# WirelessPower.net
KiCad netlist of a schematic drawn in Altium Designer
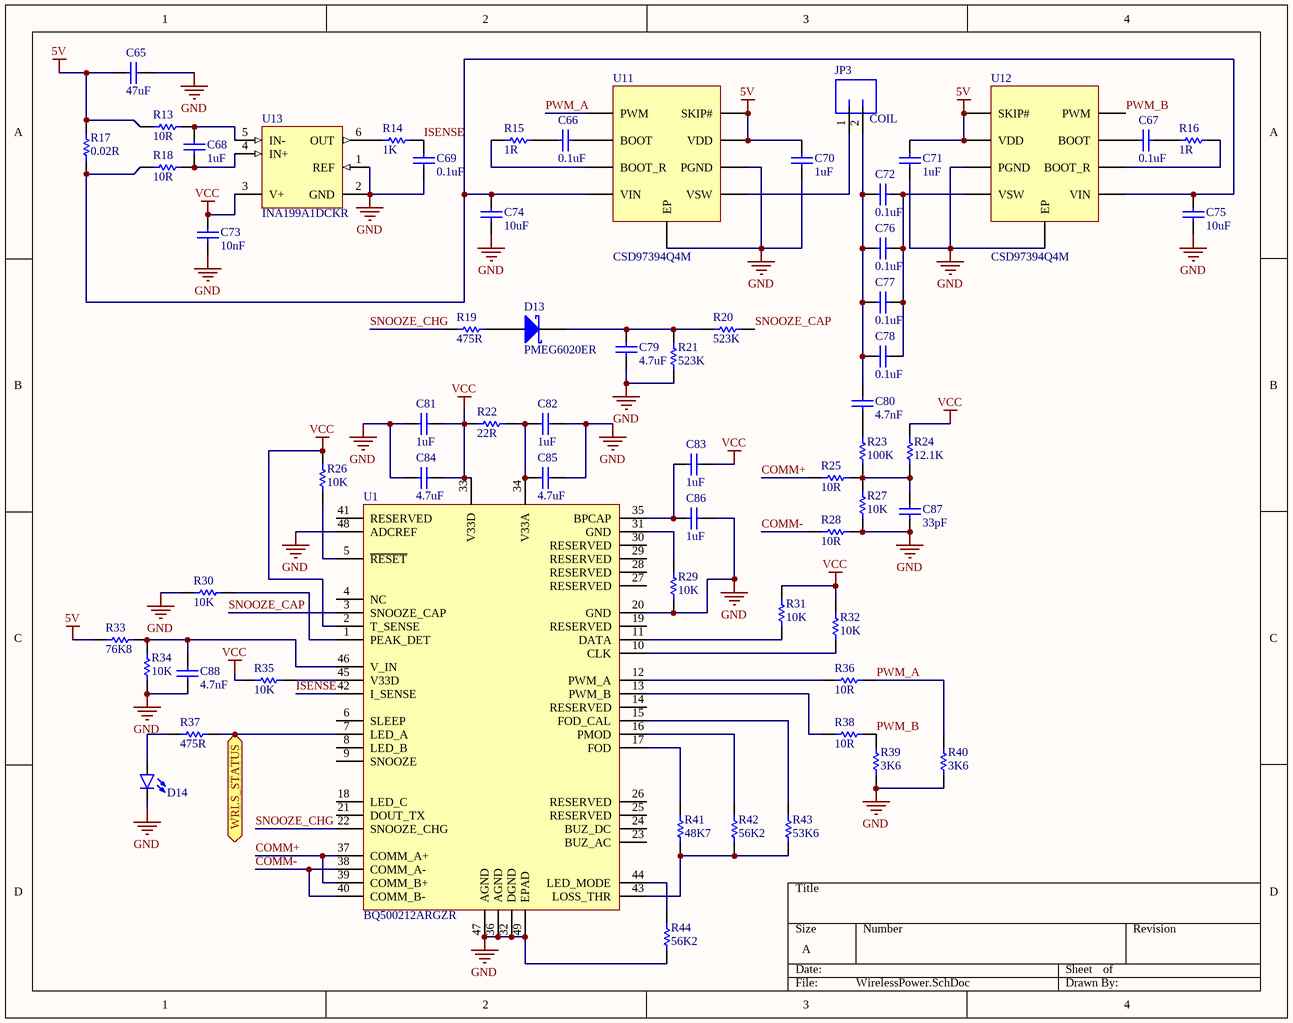
[diagram p0: WirelessPower.SchDoc]

(export (version "E")
  (design (tool "Eeschema 10.0.6"))
  (components
    (comp (ref "C65")
      (value "47uF")
      (footprint "C1210[3225X250]")
      (description "47uF 6.3V 10% 1210 (3225 Metric)")
      (fields (field (name "PARTNUMBER") "GRM32ER70J476KE20L") (field (name "MANUFACTURER") "Murata"))
      (libsource (lib "Capacitors") (part "CAP_47uF_6.3V_1210_10%"))
    )
    (comp (ref "C66")
      (value "0.1uF")
      (footprint "C0402[1005X55]")
      (description "0.1uF 100V 10% 0402 (1005 Metric)")
      (fields (field (name "PARTNUMBER") "GRM155R62A104KE14D") (field (name "MANUFACTURER") "Murata"))
      (libsource (lib "Capacitors") (part "CAP_0.1uF_100V_0402_10%"))
    )
    (comp (ref "C67")
      (value "0.1uF")
      (footprint "C0402[1005X55]")
      (description "0.1uF 100V 10% 0402 (1005 Metric)")
      (fields (field (name "PARTNUMBER") "GRM155R62A104KE14D") (field (name "MANUFACTURER") "Murata"))
      (libsource (lib "Capacitors") (part "CAP_0.1uF_100V_0402_10%"))
    )
    (comp (ref "C68")
      (value "1uF")
      (footprint "C0402[1005X55]")
      (description "1uF 6.3V 10% 0402 (1005 Metric)")
      (fields (field (name "PARTNUMBER") "GRM155R70J105KA12D") (field (name "MANUFACTURER") "Murata"))
      (libsource (lib "Capacitors") (part "CAP_1uF_6.3V_0402_10%"))
    )
    (comp (ref "C69")
      (value "0.1uF")
      (footprint "C0402[1005X55]")
      (description "0.1uF 6.3V 10% 0402 (1005 Metric)")
      (fields (field (name "PARTNUMBER") "GRM155R70J104KA01D") (field (name "MANUFACTURER") "Murata"))
      (libsource (lib "Capacitors") (part "CAP_0.1uF_6.3V_0402_10%"))
    )
    (comp (ref "C70")
      (value "1uF")
      (footprint "C0402[1005X55]")
      (description "1uF 6.3V 10% 0402 (1005 Metric)")
      (fields (field (name "PARTNUMBER") "GRM155R70J105KA12D") (field (name "MANUFACTURER") "Murata"))
      (libsource (lib "Capacitors") (part "CAP_1uF_6.3V_0402_10%"))
    )
    (comp (ref "C71")
      (value "1uF")
      (footprint "C0402[1005X55]")
      (description "1uF 6.3V 10% 0402 (1005 Metric)")
      (fields (field (name "PARTNUMBER") "GRM155R70J105KA12D") (field (name "MANUFACTURER") "Murata"))
      (libsource (lib "Capacitors") (part "CAP_1uF_6.3V_0402_10%"))
    )
    (comp (ref "C72")
      (value "0.1uF")
      (footprint "C0402[1005X55]")
      (description "0.1uF 100V 10% 0402 (1005 Metric)")
      (fields (field (name "PARTNUMBER") "GRM155R62A104KE14D") (field (name "MANUFACTURER") "Murata"))
      (libsource (lib "Capacitors") (part "CAP_0.1uF_100V_0402_10%"))
    )
    (comp (ref "C73")
      (value "10nF")
      (footprint "C0402[1005X55]")
      (description "10nF 50V 10% 0402 (1005 Metric)")
      (fields (field (name "PARTNUMBER") "GCM155R71H103KA55D") (field (name "MANUFACTURER") "Murata"))
      (libsource (lib "Capacitors") (part "CAP_10nF_50V_0402_10%"))
    )
    (comp (ref "C74")
      (value "10uF")
      (footprint "C0603[1608X92]")
      (description "10uF 16V 10% 0603 (1608 Metric)")
      (fields (field (name "PARTNUMBER") "GRM188R61C106KAALD") (field (name "MANUFACTURER") "Murata"))
      (libsource (lib "Capacitors") (part "CAP_10uF_16V_0603_10%"))
    )
    (comp (ref "C75")
      (value "10uF")
      (footprint "C0603[1608X92]")
      (description "10uF 16V 10% 0603 (1608 Metric)")
      (fields (field (name "PARTNUMBER") "GRM188R61C106KAALD") (field (name "MANUFACTURER") "Murata"))
      (libsource (lib "Capacitors") (part "CAP_10uF_16V_0603_10%"))
    )
    (comp (ref "C76")
      (value "0.1uF")
      (footprint "C0402[1005X55]")
      (description "0.1uF 100V 10% 0402 (1005 Metric)")
      (fields (field (name "PARTNUMBER") "GRM155R62A104KE14D") (field (name "MANUFACTURER") "Murata"))
      (libsource (lib "Capacitors") (part "CAP_0.1uF_100V_0402_10%"))
    )
    (comp (ref "C77")
      (value "0.1uF")
      (footprint "C0402[1005X55]")
      (description "0.1uF 100V 10% 0402 (1005 Metric)")
      (fields (field (name "PARTNUMBER") "GRM155R62A104KE14D") (field (name "MANUFACTURER") "Murata"))
      (libsource (lib "Capacitors") (part "CAP_0.1uF_100V_0402_10%"))
    )
    (comp (ref "C78")
      (value "0.1uF")
      (footprint "C0402[1005X55]")
      (description "0.1uF 100V 10% 0402 (1005 Metric)")
      (fields (field (name "PARTNUMBER") "GRM155R62A104KE14D") (field (name "MANUFACTURER") "Murata"))
      (libsource (lib "Capacitors") (part "CAP_0.1uF_100V_0402_10%"))
    )
    (comp (ref "C79")
      (value "4.7uF")
      (footprint "C0402[1005X55]")
      (description "4.7uF 6.3V 20% 0402 (1005 Metric)")
      (fields (field (name "PARTNUMBER") "GRM155R60J475ME47D") (field (name "MANUFACTURER") "Murata"))
      (libsource (lib "Capacitors") (part "CAP_4.7uF_6.3V_0402_20%"))
    )
    (comp (ref "C80")
      (value "4.7nF")
      (footprint "C0402[1005X55]")
      (description "4.7nF 50V 10% 0402 (1005 Metric)")
      (fields (field (name "PARTNUMBER") "GRM155R71H472KA01D") (field (name "MANUFACTURER") "Murata"))
      (libsource (lib "Capacitors") (part "CAP_4.7nF_50V_0402_10%"))
    )
    (comp (ref "C81")
      (value "1uF")
      (footprint "C0402[1005X55]")
      (description "1uF 6.3V 10% 0402 (1005 Metric)")
      (fields (field (name "PARTNUMBER") "GRM155R70J105KA12D") (field (name "MANUFACTURER") "Murata"))
      (libsource (lib "Capacitors") (part "CAP_1uF_6.3V_0402_10%"))
    )
    (comp (ref "C82")
      (value "1uF")
      (footprint "C0402[1005X55]")
      (description "1uF 6.3V 10% 0402 (1005 Metric)")
      (fields (field (name "PARTNUMBER") "GRM155R70J105KA12D") (field (name "MANUFACTURER") "Murata"))
      (libsource (lib "Capacitors") (part "CAP_1uF_6.3V_0402_10%"))
    )
    (comp (ref "C83")
      (value "1uF")
      (footprint "C0402[1005X55]")
      (description "1uF 6.3V 10% 0402 (1005 Metric)")
      (fields (field (name "PARTNUMBER") "GRM155R70J105KA12D") (field (name "MANUFACTURER") "Murata"))
      (libsource (lib "Capacitors") (part "CAP_1uF_6.3V_0402_10%"))
    )
    (comp (ref "C84")
      (value "4.7uF")
      (footprint "C0402[1005X55]")
      (description "4.7uF 6.3V 20% 0402 (1005 Metric)")
      (fields (field (name "PARTNUMBER") "GRM155R60J475ME47D") (field (name "MANUFACTURER") "Murata"))
      (libsource (lib "Capacitors") (part "CAP_4.7uF_6.3V_0402_20%"))
    )
    (comp (ref "C85")
      (value "4.7uF")
      (footprint "C0402[1005X55]")
      (description "4.7uF 6.3V 20% 0402 (1005 Metric)")
      (fields (field (name "PARTNUMBER") "GRM155R60J475ME47D") (field (name "MANUFACTURER") "Murata"))
      (libsource (lib "Capacitors") (part "CAP_4.7uF_6.3V_0402_20%"))
    )
    (comp (ref "C86")
      (value "1uF")
      (footprint "C0402[1005X55]")
      (description "1uF 6.3V 10% 0402 (1005 Metric)")
      (fields (field (name "PARTNUMBER") "GRM155R70J105KA12D") (field (name "MANUFACTURER") "Murata"))
      (libsource (lib "Capacitors") (part "CAP_1uF_6.3V_0402_10%"))
    )
    (comp (ref "C87")
      (value "33pF")
      (footprint "C0402[1005X55]")
      (description "33pF 50V 1% 0402 (1005 Metric)")
      (fields (field (name "PARTNUMBER") "GCM1555C1H330FA16D") (field (name "MANUFACTURER") "Murata"))
      (libsource (lib "Capacitors") (part "CAP_33pF_50V_0402_1%"))
    )
    (comp (ref "C88")
      (value "4.7nF")
      (footprint "C0402[1005X55]")
      (description "4.7nF 50V 10% 0402 (1005 Metric)")
      (fields (field (name "PARTNUMBER") "GRM155R71H472KA01D") (field (name "MANUFACTURER") "Murata"))
      (libsource (lib "Capacitors") (part "CAP_4.7nF_50V_0402_10%"))
    )
    (comp (ref "D13")
      (value "PMEG6020ER")
      (footprint "SOD-123")
      (fields (field (name "PARTNUMBER") "PMEG6020ER,115") (field (name "MANUFACTURER") "NXP Semiconductors"))
      (libsource (lib "Diodes") (part "PMEG6020ER"))
    )
    (comp (ref "D14")
      (value "LED_0603_GREEN_5mA")
      (footprint "LED0603")
      (fields (field (name "PARTNUMBER") "LTST-C193TGKT-5A") (field (name "MANUFACTURER") "Lite-On Inc."))
      (libsource (lib "LEDs") (part "LED_0603_GREEN_5mA"))
    )
    (comp (ref "JP3")
      (value "COIL")
      (footprint "JST-SH-2-SMD-HORZ")
      (fields
        (field (name "MANUFACTURER") "JST Sales America, Inc.")
        (field (name "PARTNUMBER") "SM02B-SRSS-TB")
      )
      (libsource (lib "Connectors") (part "JST_SH_2_HORZ"))
    )
    (comp (ref "R13")
      (value "10R")
      (footprint "R0402[1005]")
      (description "10R 0.063W 1% 0402 (1005 Metric)")
      (fields (field (name "MANUFACTURER") "KOA Speer") (field (name "PARTNUMBER") "RK73H1ETTP10R0F"))
      (libsource (lib "Resistors") (part "RES_10R_0402_1%"))
    )
    (comp (ref "R14")
      (value "1K")
      (footprint "R0402[1005]")
      (description "1K 0.063W 1% 0402 (1005 Metric)")
      (fields (field (name "MANUFACTURER") "KOA Speer") (field (name "PARTNUMBER") "RK73H1ETTP1001F"))
      (libsource (lib "Resistors") (part "RES_1K_0402_1%"))
    )
    (comp (ref "R15")
      (value "1R")
      (footprint "R0402[1005]")
      (description "1R 0.063W 1% 0402 (1005 Metric)")
      (fields (field (name "MANUFACTURER") "KOA Speer") (field (name "PARTNUMBER") "RK73H1ETTP1R00F"))
      (libsource (lib "Resistors") (part "RES_1R_0402_1%"))
    )
    (comp (ref "R16")
      (value "1R")
      (footprint "R0402[1005]")
      (description "1R 0.063W 1% 0402 (1005 Metric)")
      (fields (field (name "MANUFACTURER") "KOA Speer") (field (name "PARTNUMBER") "RK73H1ETTP1R00F"))
      (libsource (lib "Resistors") (part "RES_1R_0402_1%"))
    )
    (comp (ref "R17")
      (value "0.02R")
      (footprint "R0805[2012]")
      (description "0.02R 0.5W 1% 0805 (2012 Metric)")
      (fields (field (name "MANUFACTURER") "Bourns") (field (name "PARTNUMBER") "CRF0805-FZ-R020ELF"))
      (libsource (lib "Resistors") (part "RES_0.02R_0805_1%"))
    )
    (comp (ref "R18")
      (value "10R")
      (footprint "R0402[1005]")
      (description "10R 0.063W 1% 0402 (1005 Metric)")
      (fields (field (name "MANUFACTURER") "KOA Speer") (field (name "PARTNUMBER") "RK73H1ETTP10R0F"))
      (libsource (lib "Resistors") (part "RES_10R_0402_1%"))
    )
    (comp (ref "R19")
      (value "475R")
      (footprint "R0402[1005]")
      (description "475R 0.063W 1% 0402 (1005 Metric)")
      (fields (field (name "MANUFACTURER") "KOA Speer") (field (name "PARTNUMBER") "RK73H1ETTP4750F"))
      (libsource (lib "Resistors") (part "RES_475R_0402_1%"))
    )
    (comp (ref "R20")
      (value "523K")
      (footprint "R0402[1005]")
      (description "523K 0.063W 1% 0402 (1005 Metric)")
      (fields (field (name "MANUFACTURER") "KOA Speer") (field (name "PARTNUMBER") "RK73H1ETTP5233F"))
      (libsource (lib "Resistors") (part "RES_523K_0402_1%"))
    )
    (comp (ref "R21")
      (value "523K")
      (footprint "R0402[1005]")
      (description "523K 0.063W 1% 0402 (1005 Metric)")
      (fields (field (name "MANUFACTURER") "KOA Speer") (field (name "PARTNUMBER") "RK73H1ETTP5233F"))
      (libsource (lib "Resistors") (part "RES_523K_0402_1%"))
    )
    (comp (ref "R22")
      (value "22R")
      (footprint "R0402[1005]")
      (description "22R 0.063W 1% 0402 (1005 Metric)")
      (fields (field (name "MANUFACTURER") "KOA Speer") (field (name "PARTNUMBER") "RK73H1ETTP22R0F"))
      (libsource (lib "Resistors") (part "RES_22R_0402_1%"))
    )
    (comp (ref "R23")
      (value "100K")
      (footprint "R0402[1005]")
      (description "100K 0.063W 1% 0402 (1005 Metric)")
      (fields (field (name "MANUFACTURER") "KOA Speer") (field (name "PARTNUMBER") "RK73H1ETTP1003F"))
      (libsource (lib "Resistors") (part "RES_100K_0402_1%"))
    )
    (comp (ref "R24")
      (value "12.1K")
      (footprint "R0402[1005]")
      (description "12.1K 0.063W 1% 0402 (1005 Metric)")
      (fields (field (name "MANUFACTURER") "KOA Speer") (field (name "PARTNUMBER") "RK73H1ETTP1212F"))
      (libsource (lib "Resistors") (part "RES_12.1K_0402_1%"))
    )
    (comp (ref "R25")
      (value "10R")
      (footprint "R0402[1005]")
      (description "10R 0.063W 1% 0402 (1005 Metric)")
      (fields (field (name "MANUFACTURER") "KOA Speer") (field (name "PARTNUMBER") "RK73H1ETTP10R0F"))
      (libsource (lib "Resistors") (part "RES_10R_0402_1%"))
    )
    (comp (ref "R26")
      (value "10K")
      (footprint "R0402[1005]")
      (description "10K 0.063W 1% 0402 (1005 Metric)")
      (fields (field (name "MANUFACTURER") "KOA Speer") (field (name "PARTNUMBER") "RK73H1ETTP1002F"))
      (libsource (lib "Resistors") (part "RES_10K_0402_1%"))
    )
    (comp (ref "R27")
      (value "10K")
      (footprint "R0402[1005]")
      (description "10K 0.063W 1% 0402 (1005 Metric)")
      (fields (field (name "MANUFACTURER") "KOA Speer") (field (name "PARTNUMBER") "RK73H1ETTP1002F"))
      (libsource (lib "Resistors") (part "RES_10K_0402_1%"))
    )
    (comp (ref "R28")
      (value "10R")
      (footprint "R0402[1005]")
      (description "10R 0.063W 1% 0402 (1005 Metric)")
      (fields (field (name "MANUFACTURER") "KOA Speer") (field (name "PARTNUMBER") "RK73H1ETTP10R0F"))
      (libsource (lib "Resistors") (part "RES_10R_0402_1%"))
    )
    (comp (ref "R29")
      (value "10K")
      (footprint "R0402[1005]")
      (description "10K 0.063W 1% 0402 (1005 Metric)")
      (fields (field (name "MANUFACTURER") "KOA Speer") (field (name "PARTNUMBER") "RK73H1ETTP1002F"))
      (libsource (lib "Resistors") (part "RES_10K_0402_1%"))
    )
    (comp (ref "R30")
      (value "10K")
      (footprint "R0402[1005]")
      (description "10K 0.063W 1% 0402 (1005 Metric)")
      (fields (field (name "MANUFACTURER") "KOA Speer") (field (name "PARTNUMBER") "RK73H1ETTP1002F"))
      (libsource (lib "Resistors") (part "RES_10K_0402_1%"))
    )
    (comp (ref "R31")
      (value "10K")
      (footprint "R0402[1005]")
      (description "10K 0.063W 1% 0402 (1005 Metric)")
      (fields (field (name "MANUFACTURER") "KOA Speer") (field (name "PARTNUMBER") "RK73H1ETTP1002F"))
      (libsource (lib "Resistors") (part "RES_10K_0402_1%"))
    )
    (comp (ref "R32")
      (value "10K")
      (footprint "R0402[1005]")
      (description "10K 0.063W 1% 0402 (1005 Metric)")
      (fields (field (name "MANUFACTURER") "KOA Speer") (field (name "PARTNUMBER") "RK73H1ETTP1002F"))
      (libsource (lib "Resistors") (part "RES_10K_0402_1%"))
    )
    (comp (ref "R33")
      (value "76K8")
      (footprint "R0402[1005]")
      (description "76K8 0.063W 1% 0402 (1005 Metric)")
      (fields (field (name "MANUFACTURER") "KOA Speer") (field (name "PARTNUMBER") "RK73H1ETTP7682F"))
      (libsource (lib "Resistors") (part "RES_76K8_0402_1%"))
    )
    (comp (ref "R34")
      (value "10K")
      (footprint "R0402[1005]")
      (description "10K 0.063W 1% 0402 (1005 Metric)")
      (fields (field (name "MANUFACTURER") "KOA Speer") (field (name "PARTNUMBER") "RK73H1ETTP1002F"))
      (libsource (lib "Resistors") (part "RES_10K_0402_1%"))
    )
    (comp (ref "R35")
      (value "10K")
      (footprint "R0402[1005]")
      (description "10K 0.063W 1% 0402 (1005 Metric)")
      (fields (field (name "MANUFACTURER") "KOA Speer") (field (name "PARTNUMBER") "RK73H1ETTP1002F"))
      (libsource (lib "Resistors") (part "RES_10K_0402_1%"))
    )
    (comp (ref "R36")
      (value "10R")
      (footprint "R0402[1005]")
      (description "10R 0.063W 1% 0402 (1005 Metric)")
      (fields (field (name "MANUFACTURER") "KOA Speer") (field (name "PARTNUMBER") "RK73H1ETTP10R0F"))
      (libsource (lib "Resistors") (part "RES_10R_0402_1%"))
    )
    (comp (ref "R37")
      (value "475R")
      (footprint "R0402[1005]")
      (description "475R 0.063W 1% 0402 (1005 Metric)")
      (fields (field (name "MANUFACTURER") "KOA Speer") (field (name "PARTNUMBER") "RK73H1ETTP4750F"))
      (libsource (lib "Resistors") (part "RES_475R_0402_1%"))
    )
    (comp (ref "R38")
      (value "10R")
      (footprint "R0402[1005]")
      (description "10R 0.063W 1% 0402 (1005 Metric)")
      (fields (field (name "MANUFACTURER") "KOA Speer") (field (name "PARTNUMBER") "RK73H1ETTP10R0F"))
      (libsource (lib "Resistors") (part "RES_10R_0402_1%"))
    )
    (comp (ref "R39")
      (value "3K6")
      (footprint "R0402[1005]")
      (description "3K6 0.063W 1% 0402 (1005 Metric)")
      (fields (field (name "MANUFACTURER") "KOA Speer") (field (name "PARTNUMBER") "RK73H1ETTP3601F"))
      (libsource (lib "Resistors") (part "RES_3K6_0402_1%"))
    )
    (comp (ref "R40")
      (value "3K6")
      (footprint "R0402[1005]")
      (description "3K6 0.063W 1% 0402 (1005 Metric)")
      (fields (field (name "MANUFACTURER") "KOA Speer") (field (name "PARTNUMBER") "RK73H1ETTP3601F"))
      (libsource (lib "Resistors") (part "RES_3K6_0402_1%"))
    )
    (comp (ref "R41")
      (value "48K7")
      (footprint "R0402[1005]")
      (description "48K7 0.063W 1% 0402 (1005 Metric)")
      (fields (field (name "MANUFACTURER") "KOA Speer") (field (name "PARTNUMBER") "RK73H1ETTP4872F"))
      (libsource (lib "Resistors") (part "RES_48K7_0402_1%"))
    )
    (comp (ref "R42")
      (value "56K2")
      (footprint "R0402[1005]")
      (description "56K2 0.063W 1% 0402 (1005 Metric)")
      (fields (field (name "MANUFACTURER") "KOA Speer") (field (name "PARTNUMBER") "RK73H1ETTP5622F"))
      (libsource (lib "Resistors") (part "RES_56K2_0402_1%"))
    )
    (comp (ref "R43")
      (value "53K6")
      (footprint "R0402[1005]")
      (description "53K6 0.063W 1% 0402 (1005 Metric)")
      (fields (field (name "MANUFACTURER") "KOA Speer") (field (name "PARTNUMBER") "RK73H1ETTP5362F"))
      (libsource (lib "Resistors") (part "RES_53K6_0402_1%"))
    )
    (comp (ref "R44")
      (value "56K2")
      (footprint "R0402[1005]")
      (description "56K2 0.063W 1% 0402 (1005 Metric)")
      (fields (field (name "MANUFACTURER") "KOA Speer") (field (name "PARTNUMBER") "RK73H1ETTP5622F"))
      (libsource (lib "Resistors") (part "RES_56K2_0402_1%"))
    )
    (comp (ref "U1")
      (value "BQ500212ARGZR")
      (footprint "QFN-48 (0.5MM)")
      (description "IC, Qi Compliant Wireless Power Transmitter Manager")
      (fields (field (name "MANUFACTURER") "Texas Instruments"))
      (libsource (lib "ICs") (part "BQ500212ARGZR"))
    )
    (comp (ref "U11")
      (value "CSD97394Q4M")
      (footprint "VSON-CLIP")
      (fields (field (name "MANUFACTURER") "Texas Instruments"))
      (libsource (lib "ICs") (part "CSD97394Q4M"))
    )
    (comp (ref "U12")
      (value "CSD97394Q4M")
      (footprint "VSON-CLIP")
      (fields (field (name "MANUFACTURER") "Texas Instruments"))
      (libsource (lib "") (part "CSD97394Q4M_1"))
    )
    (comp (ref "U13")
      (value "INA199A1DCKR")
      (footprint "DCK0006A_M")
      (libsource (lib "Altium Content Vault") (part "TI-INA21X_199A-DCK-6"))
    )
  )
  (nets
    (net (code "1") (name "/COMM+") (class "Default")
      (node (ref "R25") (pin "1") (pinfunction "1_1") (pintype "passive"))
      (node (ref "U1") (pin "37") (pinfunction "COMM_A+_37") (pintype "passive"))
      (node (ref "U1") (pin "39") (pinfunction "COMM_B+_39") (pintype "passive"))
    )
    (net (code "2") (name "/COMM-") (class "Default")
      (node (ref "R28") (pin "1") (pinfunction "1_1") (pintype "passive"))
      (node (ref "U1") (pin "38") (pinfunction "COMM_A-_38") (pintype "passive"))
      (node (ref "U1") (pin "40") (pinfunction "COMM_B-_40") (pintype "passive"))
    )
    (net (code "3") (name "/ISENSE") (class "Default")
      (node (ref "C69") (pin "2") (pinfunction "2_2") (pintype "passive"))
      (node (ref "R14") (pin "2") (pinfunction "2_2") (pintype "passive"))
      (node (ref "U1") (pin "42") (pinfunction "I_SENSE_42") (pintype "passive"))
    )
    (net (code "4") (name "/PWM_A") (class "Default")
      (node (ref "R36") (pin "2") (pinfunction "2_2") (pintype "passive"))
      (node (ref "R40") (pin "2") (pinfunction "2_2") (pintype "passive"))
      (node (ref "U11") (pin "8") (pinfunction "PWM_8") (pintype "passive"))
    )
    (net (code "5") (name "/PWM_B") (class "Default")
      (node (ref "R38") (pin "2") (pinfunction "2_2") (pintype "passive"))
      (node (ref "R39") (pin "2") (pinfunction "2_2") (pintype "passive"))
      (node (ref "U12") (pin "8") (pinfunction "PWM_8") (pintype "passive"))
    )
    (net (code "6") (name "/SNOOZE_CAP") (class "Default")
      (node (ref "R20") (pin "2") (pinfunction "2_2") (pintype "passive"))
      (node (ref "U1") (pin "3") (pinfunction "SNOOZE_CAP_3") (pintype "passive"))
    )
    (net (code "7") (name "/SNOOZE_CHG") (class "Default")
      (node (ref "R19") (pin "1") (pinfunction "1_1") (pintype "passive"))
      (node (ref "U1") (pin "22") (pinfunction "SNOOZE_CHG_22") (pintype "passive"))
    )
    (net (code "8") (name "/WRLS_STATUS") (class "Default")
      (node (ref "R37") (pin "2") (pinfunction "2_2") (pintype "passive"))
      (node (ref "U1") (pin "7") (pinfunction "LED_A_7") (pintype "passive"))
    )
    (net (code "9") (name "5V") (class "Default")
      (node (ref "C65") (pin "1") (pinfunction "1_1") (pintype "passive"))
      (node (ref "C70") (pin "2") (pinfunction "2_2") (pintype "passive"))
      (node (ref "C71") (pin "2") (pinfunction "2_2") (pintype "passive"))
      (node (ref "R13") (pin "1") (pinfunction "1_1") (pintype "passive"))
      (node (ref "R17") (pin "2") (pinfunction "2_2") (pintype "passive"))
      (node (ref "R33") (pin "1") (pinfunction "1_1") (pintype "passive"))
      (node (ref "U11") (pin "1") (pinfunction "SKIP#_1") (pintype "passive"))
      (node (ref "U11") (pin "2") (pinfunction "VDD_2") (pintype "passive"))
      (node (ref "U12") (pin "1") (pinfunction "SKIP#_1") (pintype "passive"))
      (node (ref "U12") (pin "2") (pinfunction "VDD_2") (pintype "passive"))
    )
    (net (code "10") (name "GND") (class "Default")
      (node (ref "C65") (pin "2") (pinfunction "2_2") (pintype "passive"))
      (node (ref "C69") (pin "1") (pinfunction "1_1") (pintype "passive"))
      (node (ref "C70") (pin "1") (pinfunction "1_1") (pintype "passive"))
      (node (ref "C71") (pin "1") (pinfunction "1_1") (pintype "passive"))
      (node (ref "C73") (pin "1") (pinfunction "1_1") (pintype "passive"))
      (node (ref "C74") (pin "1") (pinfunction "1_1") (pintype "passive"))
      (node (ref "C75") (pin "1") (pinfunction "1_1") (pintype "passive"))
      (node (ref "C79") (pin "1") (pinfunction "1_1") (pintype "passive"))
      (node (ref "C81") (pin "1") (pinfunction "1_1") (pintype "passive"))
      (node (ref "C82") (pin "2") (pinfunction "2_2") (pintype "passive"))
      (node (ref "C84") (pin "1") (pinfunction "1_1") (pintype "passive"))
      (node (ref "C85") (pin "2") (pinfunction "2_2") (pintype "passive"))
      (node (ref "C86") (pin "2") (pinfunction "2_2") (pintype "passive"))
      (node (ref "C87") (pin "1") (pinfunction "1_1") (pintype "passive"))
      (node (ref "C88") (pin "1") (pinfunction "1_1") (pintype "passive"))
      (node (ref "D14") (pin "C") (pinfunction "C_C") (pintype "passive"))
      (node (ref "R21") (pin "1") (pinfunction "1_1") (pintype "passive"))
      (node (ref "R27") (pin "1") (pinfunction "1_1") (pintype "passive"))
      (node (ref "R28") (pin "2") (pinfunction "2_2") (pintype "passive"))
      (node (ref "R29") (pin "1") (pinfunction "1_1") (pintype "passive"))
      (node (ref "R30") (pin "2") (pinfunction "2_2") (pintype "passive"))
      (node (ref "R34") (pin "2") (pinfunction "2_2") (pintype "passive"))
      (node (ref "R39") (pin "1") (pinfunction "1_1") (pintype "passive"))
      (node (ref "R40") (pin "1") (pinfunction "1_1") (pintype "passive"))
      (node (ref "R44") (pin "1") (pinfunction "1_1") (pintype "passive"))
      (node (ref "U1") (pin "20") (pinfunction "GND_20") (pintype "passive"))
      (node (ref "U1") (pin "32") (pinfunction "DGND_32") (pintype "passive"))
      (node (ref "U1") (pin "36") (pinfunction "AGND_36") (pintype "passive"))
      (node (ref "U1") (pin "47") (pinfunction "AGND_47") (pintype "passive"))
      (node (ref "U1") (pin "48") (pinfunction "ADCREF_48") (pintype "passive"))
      (node (ref "U1") (pin "49") (pinfunction "EPAD_49") (pintype "passive"))
      (node (ref "U11") (pin "3") (pinfunction "PGND_3") (pintype "passive"))
      (node (ref "U11") (pin "9") (pinfunction "EP_9") (pintype "passive"))
      (node (ref "U12") (pin "3") (pinfunction "PGND_3") (pintype "passive"))
      (node (ref "U12") (pin "9") (pinfunction "EP_9") (pintype "passive"))
      (node (ref "U13") (pin "1") (pinfunction "REF_1") (pintype "input"))
      (node (ref "U13") (pin "2") (pinfunction "GND_2") (pintype "power_in"))
    )
    (net (code "11") (name "Net-(C66-Pad1)") (class "Default")
      (node (ref "C66") (pin "1") (pinfunction "1_1") (pintype "passive"))
      (node (ref "R15") (pin "2") (pinfunction "2_2") (pintype "passive"))
    )
    (net (code "12") (name "Net-(C67-Pad2)") (class "Default")
      (node (ref "C67") (pin "2") (pinfunction "2_2") (pintype "passive"))
      (node (ref "R16") (pin "1") (pinfunction "1_1") (pintype "passive"))
    )
    (net (code "13") (name "Net-(C72-Pad1)") (class "Default")
      (node (ref "C72") (pin "1") (pinfunction "1_1") (pintype "passive"))
      (node (ref "C76") (pin "1") (pinfunction "1_1") (pintype "passive"))
      (node (ref "C77") (pin "1") (pinfunction "1_1") (pintype "passive"))
      (node (ref "C78") (pin "1") (pinfunction "1_1") (pintype "passive"))
      (node (ref "C80") (pin "2") (pinfunction "2_2") (pintype "passive"))
      (node (ref "JP3") (pin "2") (pinfunction "2_2") (pintype "passive"))
    )
    (net (code "14") (name "Net-(C80-Pad1)") (class "Default")
      (node (ref "C80") (pin "1") (pinfunction "1_1") (pintype "passive"))
      (node (ref "R23") (pin "2") (pinfunction "2_2") (pintype "passive"))
    )
    (net (code "15") (name "Net-(C87-Pad2)") (class "Default")
      (node (ref "C87") (pin "2") (pinfunction "2_2") (pintype "passive"))
      (node (ref "R23") (pin "1") (pinfunction "1_1") (pintype "passive"))
      (node (ref "R24") (pin "1") (pinfunction "1_1") (pintype "passive"))
      (node (ref "R25") (pin "2") (pinfunction "2_2") (pintype "passive"))
      (node (ref "R27") (pin "2") (pinfunction "2_2") (pintype "passive"))
    )
    (net (code "16") (name "Net-(D13-A)") (class "Default")
      (node (ref "D13") (pin "2") (pinfunction "A_2") (pintype "passive"))
      (node (ref "R19") (pin "2") (pinfunction "2_2") (pintype "passive"))
    )
    (net (code "17") (name "Net-(D13-K)") (class "Default")
      (node (ref "C79") (pin "2") (pinfunction "2_2") (pintype "passive"))
      (node (ref "D13") (pin "1") (pinfunction "K_1") (pintype "passive"))
      (node (ref "R20") (pin "1") (pinfunction "1_1") (pintype "passive"))
      (node (ref "R21") (pin "2") (pinfunction "2_2") (pintype "passive"))
    )
    (net (code "18") (name "Net-(D14-PadA)") (class "Default")
      (node (ref "D14") (pin "A") (pinfunction "A_A") (pintype "passive"))
      (node (ref "R37") (pin "1") (pinfunction "1_1") (pintype "passive"))
    )
    (net (code "19") (name "Net-(R29-Pad2)") (class "Default")
      (node (ref "R29") (pin "2") (pinfunction "2_2") (pintype "passive"))
      (node (ref "U1") (pin "31") (pinfunction "GND_31") (pintype "passive"))
    )
    (net (code "20") (name "Net-(R35-Pad1)") (class "Default")
      (node (ref "R35") (pin "1") (pinfunction "1_1") (pintype "passive"))
      (node (ref "U1") (pin "45") (pinfunction "V33D_45") (pintype "passive"))
    )
    (net (code "21") (name "Net-(U1-BPCAP)") (class "Default")
      (node (ref "C83") (pin "1") (pinfunction "1_1") (pintype "passive"))
      (node (ref "C86") (pin "1") (pinfunction "1_1") (pintype "passive"))
      (node (ref "U1") (pin "35") (pinfunction "BPCAP_35") (pintype "passive"))
    )
    (net (code "22") (name "Net-(U1-CLK)") (class "Default")
      (node (ref "R32") (pin "1") (pinfunction "1_1") (pintype "passive"))
      (node (ref "U1") (pin "10") (pinfunction "CLK_10") (pintype "passive"))
    )
    (net (code "23") (name "Net-(U1-DATA)") (class "Default")
      (node (ref "R31") (pin "1") (pinfunction "1_1") (pintype "passive"))
      (node (ref "U1") (pin "11") (pinfunction "DATA_11") (pintype "passive"))
    )
    (net (code "24") (name "Net-(U1-FOD)") (class "Default")
      (node (ref "R41") (pin "2") (pinfunction "2_2") (pintype "passive"))
      (node (ref "U1") (pin "17") (pinfunction "FOD_17") (pintype "passive"))
    )
    (net (code "25") (name "Net-(U1-FOD_CAL)") (class "Default")
      (node (ref "R43") (pin "2") (pinfunction "2_2") (pintype "passive"))
      (node (ref "U1") (pin "15") (pinfunction "FOD_CAL_15") (pintype "passive"))
    )
    (net (code "26") (name "Net-(U1-LED_MODE)") (class "Default")
      (node (ref "R44") (pin "2") (pinfunction "2_2") (pintype "passive"))
      (node (ref "U1") (pin "44") (pinfunction "LED_MODE_44") (pintype "passive"))
    )
    (net (code "27") (name "Net-(U1-LOSS_THR)") (class "Default")
      (node (ref "R41") (pin "1") (pinfunction "1_1") (pintype "passive"))
      (node (ref "R42") (pin "1") (pinfunction "1_1") (pintype "passive"))
      (node (ref "R43") (pin "1") (pinfunction "1_1") (pintype "passive"))
      (node (ref "U1") (pin "43") (pinfunction "LOSS_THR_43") (pintype "passive"))
    )
    (net (code "28") (name "Net-(U1-PEAK_DET)") (class "Default")
      (node (ref "R30") (pin "1") (pinfunction "1_1") (pintype "passive"))
      (node (ref "U1") (pin "1") (pinfunction "PEAK_DET_1") (pintype "passive"))
    )
    (net (code "29") (name "Net-(U1-PMOD)") (class "Default")
      (node (ref "R42") (pin "2") (pinfunction "2_2") (pintype "passive"))
      (node (ref "U1") (pin "16") (pinfunction "PMOD_16") (pintype "passive"))
    )
    (net (code "30") (name "Net-(U1-PWM_A)") (class "Default")
      (node (ref "R36") (pin "1") (pinfunction "1_1") (pintype "passive"))
      (node (ref "U1") (pin "12") (pinfunction "PWM_A_12") (pintype "passive"))
    )
    (net (code "31") (name "Net-(U1-PWM_B)") (class "Default")
      (node (ref "R38") (pin "1") (pinfunction "1_1") (pintype "passive"))
      (node (ref "U1") (pin "13") (pinfunction "PWM_B_13") (pintype "passive"))
    )
    (net (code "32") (name "Net-(U1-RESET)") (class "Default")
      (node (ref "R26") (pin "2") (pinfunction "2_2") (pintype "passive"))
      (node (ref "U1") (pin "5") (pinfunction "RESET_5") (pintype "passive"))
    )
    (net (code "33") (name "Net-(U1-V33A)") (class "Default")
      (node (ref "C82") (pin "1") (pinfunction "1_1") (pintype "passive"))
      (node (ref "C85") (pin "1") (pinfunction "1_1") (pintype "passive"))
      (node (ref "R22") (pin "2") (pinfunction "2_2") (pintype "passive"))
      (node (ref "U1") (pin "34") (pinfunction "V33A_34") (pintype "passive"))
    )
    (net (code "34") (name "Net-(U1-V_IN)") (class "Default")
      (node (ref "C88") (pin "2") (pinfunction "2_2") (pintype "passive"))
      (node (ref "R33") (pin "2") (pinfunction "2_2") (pintype "passive"))
      (node (ref "R34") (pin "1") (pinfunction "1_1") (pintype "passive"))
      (node (ref "U1") (pin "46") (pinfunction "V_IN_46") (pintype "passive"))
    )
    (net (code "35") (name "Net-(U11-BOOT)") (class "Default")
      (node (ref "C66") (pin "2") (pinfunction "2_2") (pintype "passive"))
      (node (ref "U11") (pin "7") (pinfunction "BOOT_7") (pintype "passive"))
    )
    (net (code "36") (name "Net-(U11-BOOT_R)") (class "Default")
      (node (ref "R15") (pin "1") (pinfunction "1_1") (pintype "passive"))
      (node (ref "U11") (pin "6") (pinfunction "BOOT_R_6") (pintype "passive"))
    )
    (net (code "37") (name "Net-(U11-VIN)") (class "Default")
      (node (ref "C74") (pin "2") (pinfunction "2_2") (pintype "passive"))
      (node (ref "C75") (pin "2") (pinfunction "2_2") (pintype "passive"))
      (node (ref "R17") (pin "1") (pinfunction "1_1") (pintype "passive"))
      (node (ref "R18") (pin "1") (pinfunction "1_1") (pintype "passive"))
      (node (ref "U11") (pin "5") (pinfunction "VIN_5") (pintype "passive"))
      (node (ref "U12") (pin "5") (pinfunction "VIN_5") (pintype "passive"))
    )
    (net (code "38") (name "Net-(U11-VSW)") (class "Default")
      (node (ref "JP3") (pin "1") (pinfunction "1_1") (pintype "passive"))
      (node (ref "U11") (pin "4") (pinfunction "VSW_4") (pintype "passive"))
    )
    (net (code "39") (name "Net-(U12-BOOT)") (class "Default")
      (node (ref "C67") (pin "1") (pinfunction "1_1") (pintype "passive"))
      (node (ref "U12") (pin "7") (pinfunction "BOOT_7") (pintype "passive"))
    )
    (net (code "40") (name "Net-(U12-BOOT_R)") (class "Default")
      (node (ref "R16") (pin "2") (pinfunction "2_2") (pintype "passive"))
      (node (ref "U12") (pin "6") (pinfunction "BOOT_R_6") (pintype "passive"))
    )
    (net (code "41") (name "Net-(U12-VSW)") (class "Default")
      (node (ref "C72") (pin "2") (pinfunction "2_2") (pintype "passive"))
      (node (ref "C76") (pin "2") (pinfunction "2_2") (pintype "passive"))
      (node (ref "C77") (pin "2") (pinfunction "2_2") (pintype "passive"))
      (node (ref "C78") (pin "2") (pinfunction "2_2") (pintype "passive"))
      (node (ref "U12") (pin "4") (pinfunction "VSW_4") (pintype "passive"))
    )
    (net (code "42") (name "Net-(U13-IN+)") (class "Default")
      (node (ref "C68") (pin "1") (pinfunction "1_1") (pintype "passive"))
      (node (ref "R18") (pin "2") (pinfunction "2_2") (pintype "passive"))
      (node (ref "U13") (pin "4") (pinfunction "IN+_4") (pintype "input"))
    )
    (net (code "43") (name "Net-(U13-IN-)") (class "Default")
      (node (ref "C68") (pin "2") (pinfunction "2_2") (pintype "passive"))
      (node (ref "R13") (pin "2") (pinfunction "2_2") (pintype "passive"))
      (node (ref "U13") (pin "5") (pinfunction "IN-_5") (pintype "input"))
    )
    (net (code "44") (name "Net-(U13-OUT)") (class "Default")
      (node (ref "R14") (pin "1") (pinfunction "1_1") (pintype "passive"))
      (node (ref "U13") (pin "6") (pinfunction "OUT_6") (pintype "output"))
    )
    (net (code "45") (name "VCC") (class "Default")
      (node (ref "C73") (pin "2") (pinfunction "2_2") (pintype "passive"))
      (node (ref "C81") (pin "2") (pinfunction "2_2") (pintype "passive"))
      (node (ref "C83") (pin "2") (pinfunction "2_2") (pintype "passive"))
      (node (ref "C84") (pin "2") (pinfunction "2_2") (pintype "passive"))
      (node (ref "R22") (pin "1") (pinfunction "1_1") (pintype "passive"))
      (node (ref "R24") (pin "2") (pinfunction "2_2") (pintype "passive"))
      (node (ref "R26") (pin "1") (pinfunction "1_1") (pintype "passive"))
      (node (ref "R31") (pin "2") (pinfunction "2_2") (pintype "passive"))
      (node (ref "R32") (pin "2") (pinfunction "2_2") (pintype "passive"))
      (node (ref "R35") (pin "2") (pinfunction "2_2") (pintype "passive"))
      (node (ref "U1") (pin "2") (pinfunction "T_SENSE_2") (pintype "passive"))
      (node (ref "U1") (pin "33") (pinfunction "V33D_33") (pintype "passive"))
      (node (ref "U13") (pin "3") (pinfunction "V+_3") (pintype "power_in"))
    )
    (net (code "46") (name "unconnected-(U1-BUZ_AC-Pad23)") (class "Default")
      (node (ref "U1") (pin "23") (pinfunction "BUZ_AC_23") (pintype "passive"))
    )
    (net (code "47") (name "unconnected-(U1-BUZ_DC-Pad24)") (class "Default")
      (node (ref "U1") (pin "24") (pinfunction "BUZ_DC_24") (pintype "passive"))
    )
    (net (code "48") (name "unconnected-(U1-DOUT_TX-Pad21)") (class "Default")
      (node (ref "U1") (pin "21") (pinfunction "DOUT_TX_21") (pintype "passive"))
    )
    (net (code "49") (name "unconnected-(U1-LED_B-Pad8)") (class "Default")
      (node (ref "U1") (pin "8") (pinfunction "LED_B_8") (pintype "passive"))
    )
    (net (code "50") (name "unconnected-(U1-LED_C-Pad18)") (class "Default")
      (node (ref "U1") (pin "18") (pinfunction "LED_C_18") (pintype "passive"))
    )
    (net (code "51") (name "unconnected-(U1-NC-Pad4)") (class "Default")
      (node (ref "U1") (pin "4") (pinfunction "NC_4") (pintype "passive"))
    )
    (net (code "52") (name "unconnected-(U1-RESERVED-Pad14)") (class "Default")
      (node (ref "U1") (pin "14") (pinfunction "RESERVED_14") (pintype "passive"))
    )
    (net (code "53") (name "unconnected-(U1-RESERVED-Pad19)") (class "Default")
      (node (ref "U1") (pin "19") (pinfunction "RESERVED_19") (pintype "passive"))
    )
    (net (code "54") (name "unconnected-(U1-RESERVED-Pad25)") (class "Default")
      (node (ref "U1") (pin "25") (pinfunction "RESERVED_25") (pintype "passive"))
    )
    (net (code "55") (name "unconnected-(U1-RESERVED-Pad26)") (class "Default")
      (node (ref "U1") (pin "26") (pinfunction "RESERVED_26") (pintype "passive"))
    )
    (net (code "56") (name "unconnected-(U1-RESERVED-Pad27)") (class "Default")
      (node (ref "U1") (pin "27") (pinfunction "RESERVED_27") (pintype "passive"))
    )
    (net (code "57") (name "unconnected-(U1-RESERVED-Pad28)") (class "Default")
      (node (ref "U1") (pin "28") (pinfunction "RESERVED_28") (pintype "passive"))
    )
    (net (code "58") (name "unconnected-(U1-RESERVED-Pad29)") (class "Default")
      (node (ref "U1") (pin "29") (pinfunction "RESERVED_29") (pintype "passive"))
    )
    (net (code "59") (name "unconnected-(U1-RESERVED-Pad30)") (class "Default")
      (node (ref "U1") (pin "30") (pinfunction "RESERVED_30") (pintype "passive"))
    )
    (net (code "60") (name "unconnected-(U1-RESERVED-Pad41)") (class "Default")
      (node (ref "U1") (pin "41") (pinfunction "RESERVED_41") (pintype "passive"))
    )
    (net (code "61") (name "unconnected-(U1-SLEEP-Pad6)") (class "Default")
      (node (ref "U1") (pin "6") (pinfunction "SLEEP_6") (pintype "passive"))
    )
    (net (code "62") (name "unconnected-(U1-SNOOZE-Pad9)") (class "Default")
      (node (ref "U1") (pin "9") (pinfunction "SNOOZE_9") (pintype "passive"))
    )
  )
)
